# SCH_milkv-extension-board_2024-06-30.net
KiCad netlist of a schematic drawn in EasyEDA
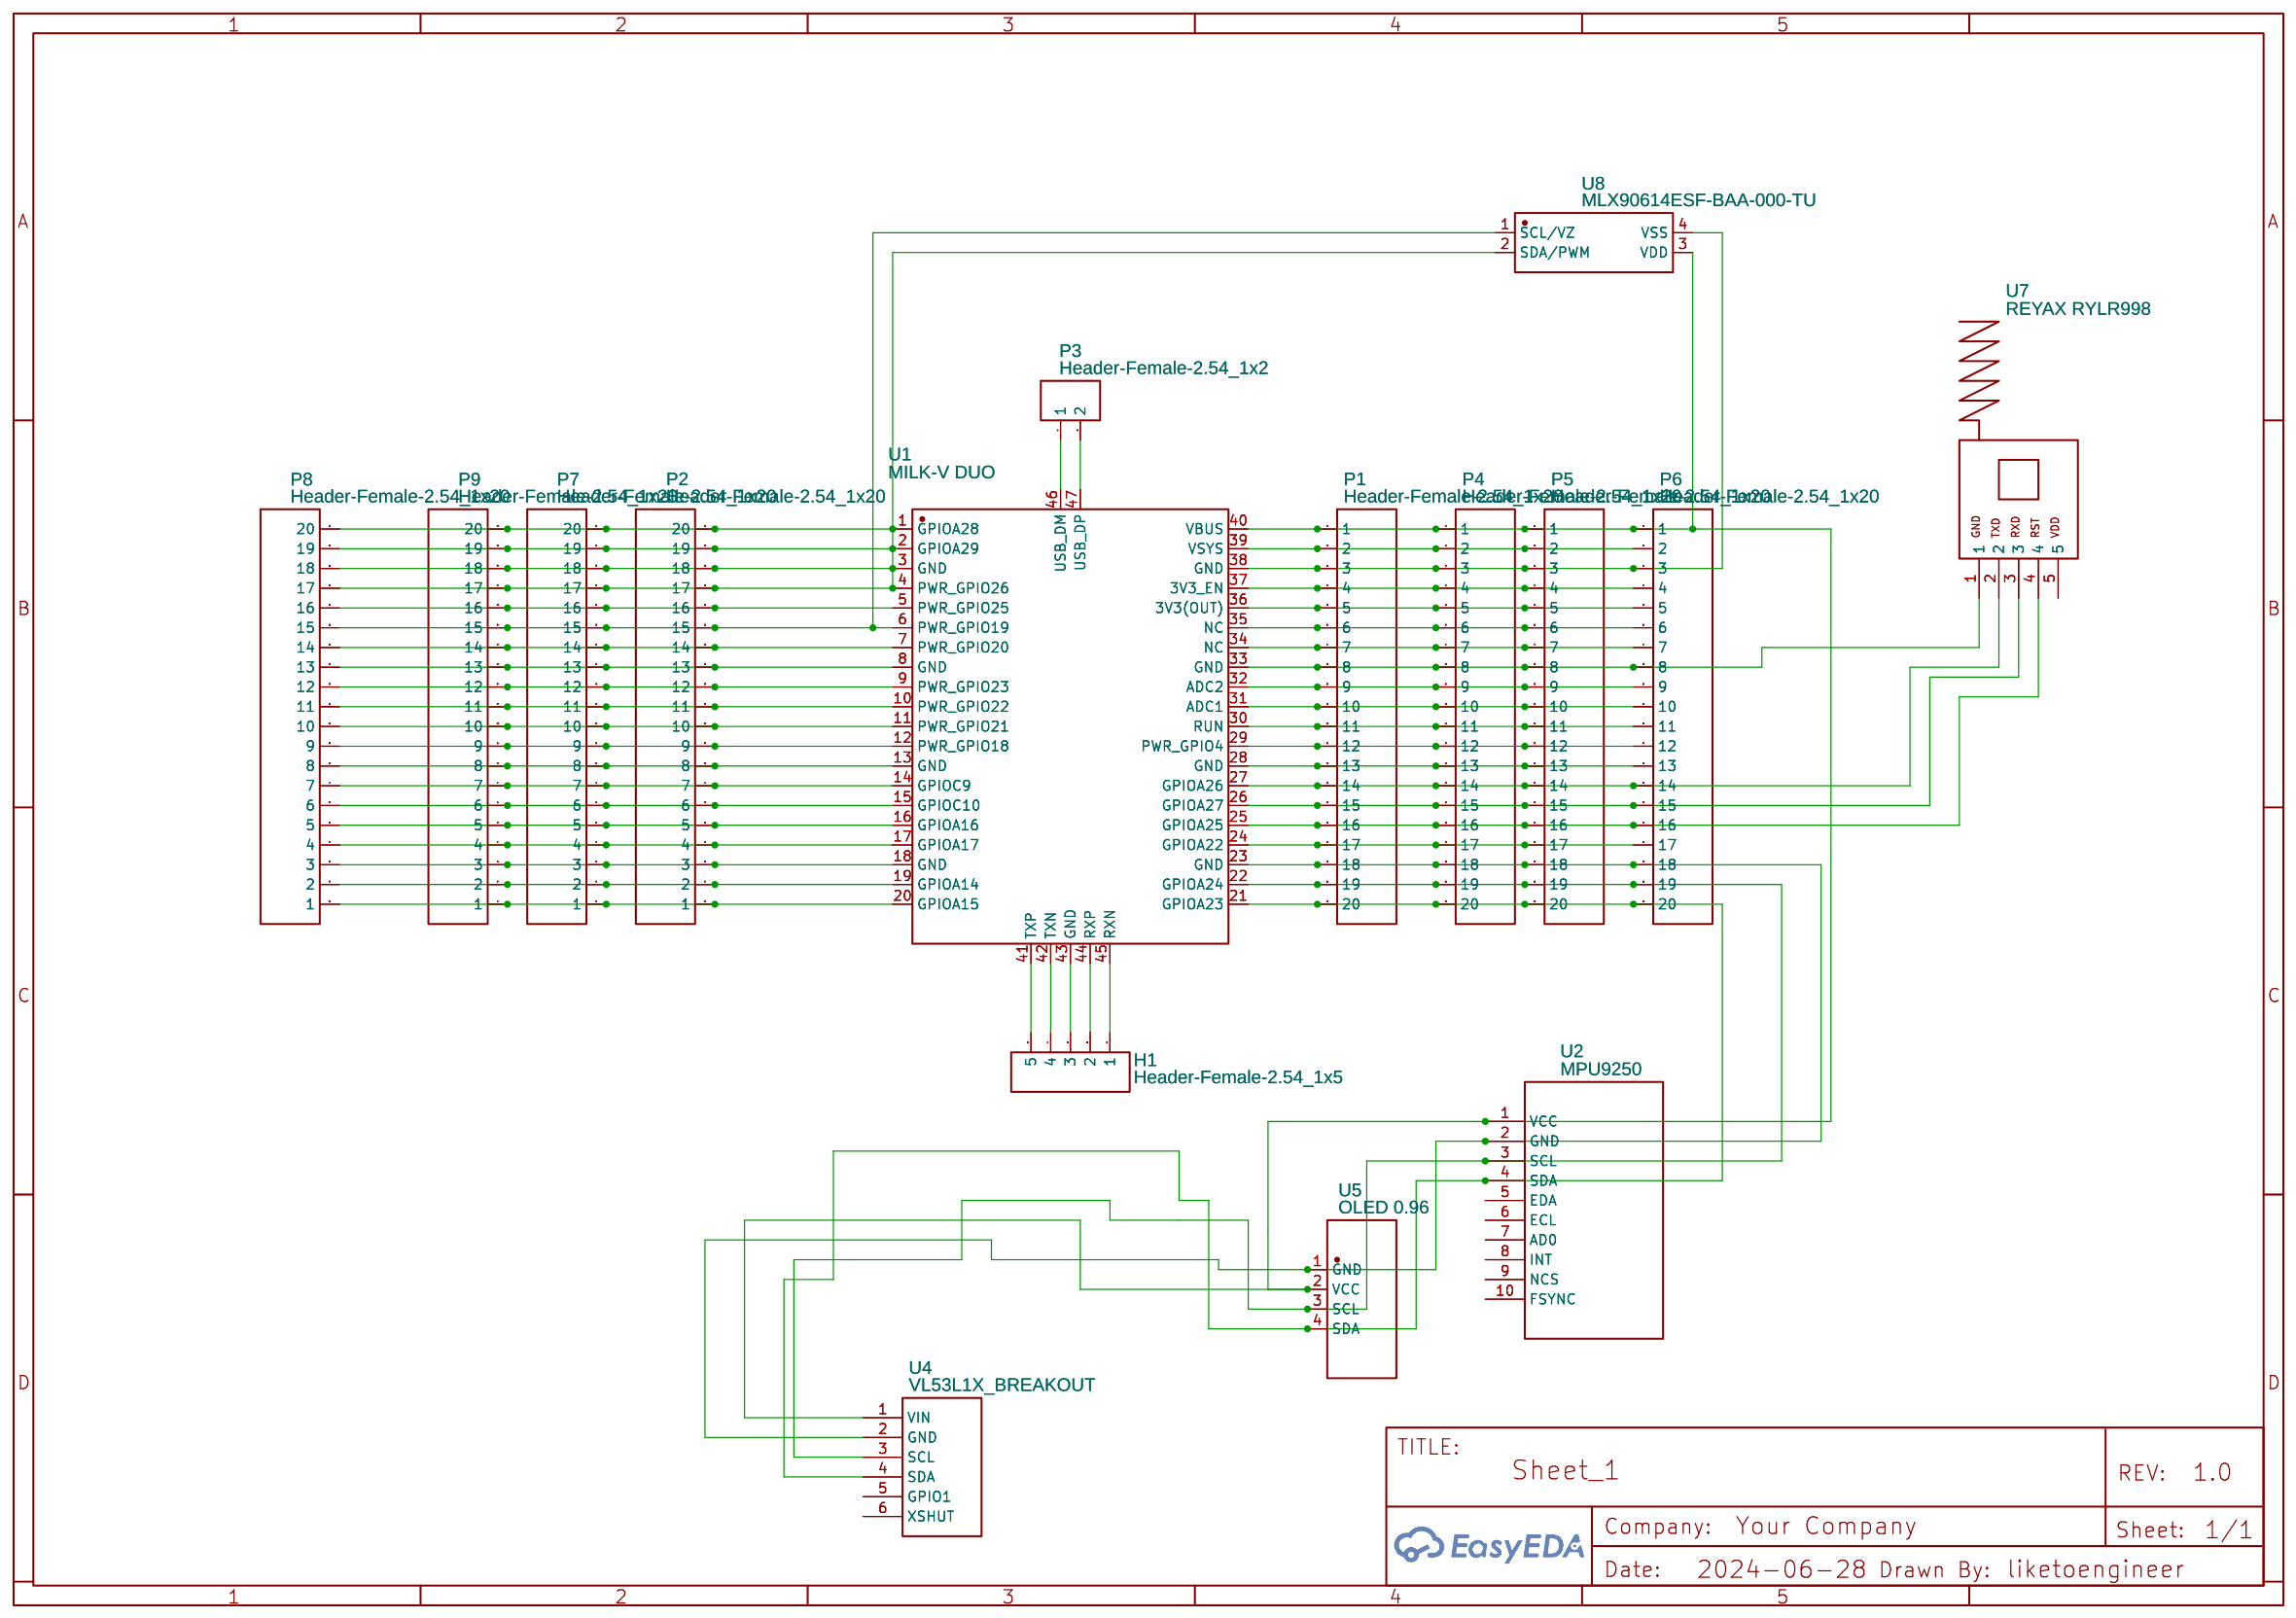
[diagram p0: schematic sheet]

(export (version "E")
  (design (tool "Eeschema 10.0.6"))
  (components
    (comp (ref "H1")
      (value "Header-Female-2.54_1x5")
      (fields (field (name "Manufacturer Part") "2.54-1*5P母") (field (name "Manufacturer") "BOOMELE(博穆精密)"))
      (libsource (lib "") (part "Header-Female-2.54_1x5"))
    )
    (comp (ref "P1")
      (value "Header-Female-2.54_1x20")
      (fields (field (name "Manufacturer Part") "2.54-1*20P母") (field (name "Manufacturer") "BOOMELE(博穆精密)"))
      (libsource (lib "") (part "Header-Female-2.54_1x20"))
    )
    (comp (ref "P2")
      (value "Header-Female-2.54_1x20")
      (fields (field (name "Manufacturer Part") "2.54-1*20P母") (field (name "Manufacturer") "BOOMELE(博穆精密)"))
      (libsource (lib "") (part "Header-Female-2.54_1x20_1"))
    )
    (comp (ref "P3")
      (value "Header-Female-2.54_1x2")
      (fields (field (name "Manufacturer Part") "2.54-1*2P母") (field (name "Manufacturer") "BOOMELE(博穆精密)"))
      (libsource (lib "") (part "Header-Female-2.54_1x2"))
    )
    (comp (ref "P4")
      (value "Header-Female-2.54_1x20")
      (fields (field (name "Manufacturer Part") "2.54-1*20P母") (field (name "Manufacturer") "BOOMELE(博穆精密)"))
      (libsource (lib "") (part "Header-Female-2.54_1x20"))
    )
    (comp (ref "P5")
      (value "Header-Female-2.54_1x20")
      (fields (field (name "Manufacturer Part") "2.54-1*20P母") (field (name "Manufacturer") "BOOMELE(博穆精密)"))
      (libsource (lib "") (part "Header-Female-2.54_1x20"))
    )
    (comp (ref "P6")
      (value "Header-Female-2.54_1x20")
      (fields (field (name "Manufacturer Part") "2.54-1*20P母") (field (name "Manufacturer") "BOOMELE(博穆精密)"))
      (libsource (lib "") (part "Header-Female-2.54_1x20"))
    )
    (comp (ref "P7")
      (value "Header-Female-2.54_1x20")
      (fields (field (name "Manufacturer Part") "2.54-1*20P母") (field (name "Manufacturer") "BOOMELE(博穆精密)"))
      (libsource (lib "") (part "Header-Female-2.54_1x20_1"))
    )
    (comp (ref "P8")
      (value "Header-Female-2.54_1x20")
      (fields (field (name "Manufacturer Part") "2.54-1*20P母") (field (name "Manufacturer") "BOOMELE(博穆精密)"))
      (libsource (lib "") (part "Header-Female-2.54_1x20_1"))
    )
    (comp (ref "P9")
      (value "Header-Female-2.54_1x20")
      (fields (field (name "Manufacturer Part") "2.54-1*20P母") (field (name "Manufacturer") "BOOMELE(博穆精密)"))
      (libsource (lib "") (part "Header-Female-2.54_1x20_1"))
    )
    (comp (ref "U1")
      (value "MILK-V DUO")
      (fields (field (name "Manufacturer Part") "Milk-V Duo"))
      (libsource (lib "") (part "MILK-V DUO"))
    )
    (comp (ref "U2") (value "MPU9250") (libsource (lib "") (part "MPU9250")))
    (comp (ref "U4")
      (value "VL53L1X_BREAKOUT")
      (fields (field (name "Manufacturer Part") "VL53L0X Time-of-Flight Distance Sensor VL53L0X"))
      (libsource (lib "") (part "VL53L1X_BREAKOUT"))
    )
    (comp (ref "U5")
      (value "OLED 0.96")
      (fields
        (field (name "Manufacturer Part") "ZJY096S0700BG01蓝色")
        (field (name "Manufacturer") "郑州中景园电子技术有限公司")
      )
      (libsource (lib "") (part "OLED 0.96"))
    )
    (comp (ref "U7")
      (value "REYAX RYLR998")
      (fields (field (name "Manufacturer Part") "RYLR998") (field (name "Manufacturer") "REYAX"))
      (libsource (lib "") (part "REYAX RYLR998"))
    )
    (comp (ref "U8")
      (value "MLX90614ESF-BAA-000-TU")
      (fields (field (name "Manufacturer") "Melexis(比利时迈来芯)"))
      (libsource (lib "") (part "MLX90614ESF-BAA-000-TU"))
    )
  )
  (nets
    (net (code "1") (name "Net-(H1-Pad3)") (class "Default")
      (node (ref "H1") (pin "3") (pinfunction "3_3") (pintype "input"))
      (node (ref "U1") (pin "43") (pinfunction "GND_43") (pintype "unspecified"))
    )
    (net (code "2") (name "Net-(P1-Pad6)") (class "Default")
      (node (ref "P1") (pin "6") (pinfunction "6_6") (pintype "input"))
      (node (ref "P4") (pin "6") (pinfunction "6_6") (pintype "input"))
      (node (ref "P5") (pin "6") (pinfunction "6_6") (pintype "input"))
      (node (ref "P6") (pin "6") (pinfunction "6_6") (pintype "input"))
      (node (ref "U1") (pin "35") (pinfunction "NC_35") (pintype "unspecified"))
    )
    (net (code "3") (name "Net-(P1-Pad7)") (class "Default")
      (node (ref "P1") (pin "7") (pinfunction "7_7") (pintype "input"))
      (node (ref "P4") (pin "7") (pinfunction "7_7") (pintype "input"))
      (node (ref "P5") (pin "7") (pinfunction "7_7") (pintype "input"))
      (node (ref "P6") (pin "7") (pinfunction "7_7") (pintype "input"))
      (node (ref "U1") (pin "34") (pinfunction "NC_34") (pintype "unspecified"))
    )
    (net (code "4") (name "Net-(P1-Pad8)") (class "Default")
      (node (ref "P1") (pin "8") (pinfunction "8_8") (pintype "input"))
      (node (ref "P4") (pin "8") (pinfunction "8_8") (pintype "input"))
      (node (ref "P5") (pin "8") (pinfunction "8_8") (pintype "input"))
      (node (ref "P6") (pin "8") (pinfunction "8_8") (pintype "input"))
      (node (ref "U1") (pin "33") (pinfunction "GND_33") (pintype "unspecified"))
      (node (ref "U7") (pin "1") (pinfunction "1_1") (pintype "unspecified"))
    )
    (net (code "5") (name "Net-(P1-Pad13)") (class "Default")
      (node (ref "P1") (pin "13") (pinfunction "13_13") (pintype "input"))
      (node (ref "P4") (pin "13") (pinfunction "13_13") (pintype "input"))
      (node (ref "P5") (pin "13") (pinfunction "13_13") (pintype "input"))
      (node (ref "P6") (pin "13") (pinfunction "13_13") (pintype "input"))
      (node (ref "U1") (pin "28") (pinfunction "GND_28") (pintype "unspecified"))
    )
    (net (code "6") (name "Net-(P2-Pad3)") (class "Default")
      (node (ref "P2") (pin "3") (pinfunction "3_3") (pintype "input"))
      (node (ref "P7") (pin "3") (pinfunction "3_3") (pintype "input"))
      (node (ref "P8") (pin "3") (pinfunction "3_3") (pintype "input"))
      (node (ref "P9") (pin "3") (pinfunction "3_3") (pintype "input"))
      (node (ref "U1") (pin "18") (pinfunction "GND_18") (pintype "unspecified"))
    )
    (net (code "7") (name "Net-(P2-Pad8)") (class "Default")
      (node (ref "P2") (pin "8") (pinfunction "8_8") (pintype "input"))
      (node (ref "P7") (pin "8") (pinfunction "8_8") (pintype "input"))
      (node (ref "P8") (pin "8") (pinfunction "8_8") (pintype "input"))
      (node (ref "P9") (pin "8") (pinfunction "8_8") (pintype "input"))
      (node (ref "U1") (pin "13") (pinfunction "GND_13") (pintype "unspecified"))
    )
    (net (code "8") (name "Net-(P2-Pad13)") (class "Default")
      (node (ref "P2") (pin "13") (pinfunction "13_13") (pintype "input"))
      (node (ref "P7") (pin "13") (pinfunction "13_13") (pintype "input"))
      (node (ref "P8") (pin "13") (pinfunction "13_13") (pintype "input"))
      (node (ref "P9") (pin "13") (pinfunction "13_13") (pintype "input"))
      (node (ref "U1") (pin "8") (pinfunction "GND_8") (pintype "unspecified"))
    )
    (net (code "9") (name "Net-(U1-3V3(OUT))") (class "Default")
      (node (ref "P1") (pin "5") (pinfunction "5_5") (pintype "input"))
      (node (ref "P4") (pin "5") (pinfunction "5_5") (pintype "input"))
      (node (ref "P5") (pin "5") (pinfunction "5_5") (pintype "input"))
      (node (ref "P6") (pin "5") (pinfunction "5_5") (pintype "input"))
      (node (ref "U1") (pin "36") (pinfunction "3V3(OUT)_36") (pintype "unspecified"))
    )
    (net (code "10") (name "Net-(U1-3V3_EN)") (class "Default")
      (node (ref "P1") (pin "4") (pinfunction "4_4") (pintype "input"))
      (node (ref "P4") (pin "4") (pinfunction "4_4") (pintype "input"))
      (node (ref "P5") (pin "4") (pinfunction "4_4") (pintype "input"))
      (node (ref "P6") (pin "4") (pinfunction "4_4") (pintype "input"))
      (node (ref "U1") (pin "37") (pinfunction "3V3_EN_37") (pintype "unspecified"))
    )
    (net (code "11") (name "Net-(U1-ADC1)") (class "Default")
      (node (ref "P1") (pin "10") (pinfunction "10_10") (pintype "input"))
      (node (ref "P4") (pin "10") (pinfunction "10_10") (pintype "input"))
      (node (ref "P5") (pin "10") (pinfunction "10_10") (pintype "input"))
      (node (ref "P6") (pin "10") (pinfunction "10_10") (pintype "input"))
      (node (ref "U1") (pin "31") (pinfunction "ADC1_31") (pintype "unspecified"))
    )
    (net (code "12") (name "Net-(U1-ADC2)") (class "Default")
      (node (ref "P1") (pin "9") (pinfunction "9_9") (pintype "input"))
      (node (ref "P4") (pin "9") (pinfunction "9_9") (pintype "input"))
      (node (ref "P5") (pin "9") (pinfunction "9_9") (pintype "input"))
      (node (ref "P6") (pin "9") (pinfunction "9_9") (pintype "input"))
      (node (ref "U1") (pin "32") (pinfunction "ADC2_32") (pintype "unspecified"))
    )
    (net (code "13") (name "Net-(U1-GPIOA14)") (class "Default")
      (node (ref "P2") (pin "2") (pinfunction "2_2") (pintype "input"))
      (node (ref "P7") (pin "2") (pinfunction "2_2") (pintype "input"))
      (node (ref "P8") (pin "2") (pinfunction "2_2") (pintype "input"))
      (node (ref "P9") (pin "2") (pinfunction "2_2") (pintype "input"))
      (node (ref "U1") (pin "19") (pinfunction "GPIOA14_19") (pintype "unspecified"))
    )
    (net (code "14") (name "Net-(U1-GPIOA15)") (class "Default")
      (node (ref "P2") (pin "1") (pinfunction "1_1") (pintype "input"))
      (node (ref "P7") (pin "1") (pinfunction "1_1") (pintype "input"))
      (node (ref "P8") (pin "1") (pinfunction "1_1") (pintype "input"))
      (node (ref "P9") (pin "1") (pinfunction "1_1") (pintype "input"))
      (node (ref "U1") (pin "20") (pinfunction "GPIOA15_20") (pintype "unspecified"))
    )
    (net (code "15") (name "Net-(U1-GPIOA16)") (class "Default")
      (node (ref "P2") (pin "5") (pinfunction "5_5") (pintype "input"))
      (node (ref "P7") (pin "5") (pinfunction "5_5") (pintype "input"))
      (node (ref "P8") (pin "5") (pinfunction "5_5") (pintype "input"))
      (node (ref "P9") (pin "5") (pinfunction "5_5") (pintype "input"))
      (node (ref "U1") (pin "16") (pinfunction "GPIOA16_16") (pintype "unspecified"))
    )
    (net (code "16") (name "Net-(U1-GPIOA17)") (class "Default")
      (node (ref "P2") (pin "4") (pinfunction "4_4") (pintype "input"))
      (node (ref "P7") (pin "4") (pinfunction "4_4") (pintype "input"))
      (node (ref "P8") (pin "4") (pinfunction "4_4") (pintype "input"))
      (node (ref "P9") (pin "4") (pinfunction "4_4") (pintype "input"))
      (node (ref "U1") (pin "17") (pinfunction "GPIOA17_17") (pintype "unspecified"))
    )
    (net (code "17") (name "Net-(U1-GPIOA22)") (class "Default")
      (node (ref "P1") (pin "17") (pinfunction "17_17") (pintype "input"))
      (node (ref "P4") (pin "17") (pinfunction "17_17") (pintype "input"))
      (node (ref "P5") (pin "17") (pinfunction "17_17") (pintype "input"))
      (node (ref "P6") (pin "17") (pinfunction "17_17") (pintype "input"))
      (node (ref "U1") (pin "24") (pinfunction "GPIOA22_24") (pintype "unspecified"))
    )
    (net (code "18") (name "Net-(U1-GPIOA23)") (class "Default")
      (node (ref "P1") (pin "20") (pinfunction "20_20") (pintype "input"))
      (node (ref "P4") (pin "20") (pinfunction "20_20") (pintype "input"))
      (node (ref "P5") (pin "20") (pinfunction "20_20") (pintype "input"))
      (node (ref "P6") (pin "20") (pinfunction "20_20") (pintype "input"))
      (node (ref "U1") (pin "21") (pinfunction "GPIOA23_21") (pintype "unspecified"))
      (node (ref "U2") (pin "4") (pinfunction "SDA_4") (pintype "unspecified"))
      (node (ref "U4") (pin "4") (pinfunction "SDA_4") (pintype "unspecified"))
      (node (ref "U5") (pin "4") (pinfunction "SDA_4") (pintype "unspecified"))
    )
    (net (code "19") (name "Net-(U1-GPIOA24)") (class "Default")
      (node (ref "P1") (pin "19") (pinfunction "19_19") (pintype "input"))
      (node (ref "P4") (pin "19") (pinfunction "19_19") (pintype "input"))
      (node (ref "P5") (pin "19") (pinfunction "19_19") (pintype "input"))
      (node (ref "P6") (pin "19") (pinfunction "19_19") (pintype "input"))
      (node (ref "U1") (pin "22") (pinfunction "GPIOA24_22") (pintype "unspecified"))
      (node (ref "U2") (pin "3") (pinfunction "SCL_3") (pintype "unspecified"))
      (node (ref "U4") (pin "3") (pinfunction "SCL_3") (pintype "unspecified"))
      (node (ref "U5") (pin "3") (pinfunction "SCL_3") (pintype "unspecified"))
    )
    (net (code "20") (name "Net-(U1-GPIOA25)") (class "Default")
      (node (ref "P1") (pin "16") (pinfunction "16_16") (pintype "input"))
      (node (ref "P4") (pin "16") (pinfunction "16_16") (pintype "input"))
      (node (ref "P5") (pin "16") (pinfunction "16_16") (pintype "input"))
      (node (ref "P6") (pin "16") (pinfunction "16_16") (pintype "input"))
      (node (ref "U1") (pin "25") (pinfunction "GPIOA25_25") (pintype "unspecified"))
      (node (ref "U7") (pin "4") (pinfunction "4_4") (pintype "unspecified"))
    )
    (net (code "21") (name "Net-(U1-GPIOA26)") (class "Default")
      (node (ref "P1") (pin "14") (pinfunction "14_14") (pintype "input"))
      (node (ref "P4") (pin "14") (pinfunction "14_14") (pintype "input"))
      (node (ref "P5") (pin "14") (pinfunction "14_14") (pintype "input"))
      (node (ref "P6") (pin "14") (pinfunction "14_14") (pintype "input"))
      (node (ref "U1") (pin "27") (pinfunction "GPIOA26_27") (pintype "unspecified"))
      (node (ref "U7") (pin "2") (pinfunction "2_2") (pintype "unspecified"))
    )
    (net (code "22") (name "Net-(U1-GPIOA27)") (class "Default")
      (node (ref "P1") (pin "15") (pinfunction "15_15") (pintype "input"))
      (node (ref "P4") (pin "15") (pinfunction "15_15") (pintype "input"))
      (node (ref "P5") (pin "15") (pinfunction "15_15") (pintype "input"))
      (node (ref "P6") (pin "15") (pinfunction "15_15") (pintype "input"))
      (node (ref "U1") (pin "26") (pinfunction "GPIOA27_26") (pintype "unspecified"))
      (node (ref "U7") (pin "3") (pinfunction "3_3") (pintype "unspecified"))
    )
    (net (code "23") (name "Net-(U1-GPIOA28)") (class "Default")
      (node (ref "P2") (pin "17") (pinfunction "17_17") (pintype "input"))
      (node (ref "P2") (pin "18") (pinfunction "18_18") (pintype "input"))
      (node (ref "P2") (pin "19") (pinfunction "19_19") (pintype "input"))
      (node (ref "P2") (pin "20") (pinfunction "20_20") (pintype "input"))
      (node (ref "P7") (pin "17") (pinfunction "17_17") (pintype "input"))
      (node (ref "P7") (pin "18") (pinfunction "18_18") (pintype "input"))
      (node (ref "P7") (pin "19") (pinfunction "19_19") (pintype "input"))
      (node (ref "P7") (pin "20") (pinfunction "20_20") (pintype "input"))
      (node (ref "P8") (pin "17") (pinfunction "17_17") (pintype "input"))
      (node (ref "P8") (pin "18") (pinfunction "18_18") (pintype "input"))
      (node (ref "P8") (pin "19") (pinfunction "19_19") (pintype "input"))
      (node (ref "P8") (pin "20") (pinfunction "20_20") (pintype "input"))
      (node (ref "P9") (pin "17") (pinfunction "17_17") (pintype "input"))
      (node (ref "P9") (pin "18") (pinfunction "18_18") (pintype "input"))
      (node (ref "P9") (pin "19") (pinfunction "19_19") (pintype "input"))
      (node (ref "P9") (pin "20") (pinfunction "20_20") (pintype "input"))
      (node (ref "U1") (pin "1") (pinfunction "GPIOA28_1") (pintype "unspecified"))
      (node (ref "U1") (pin "2") (pinfunction "GPIOA29_2") (pintype "unspecified"))
      (node (ref "U1") (pin "3") (pinfunction "GND_3") (pintype "unspecified"))
      (node (ref "U1") (pin "4") (pinfunction "PWR_GPIO26_4") (pintype "unspecified"))
      (node (ref "U8") (pin "2") (pinfunction "SDA/PWM_2") (pintype "unspecified"))
    )
    (net (code "24") (name "Net-(U1-GPIOC9)") (class "Default")
      (node (ref "P2") (pin "7") (pinfunction "7_7") (pintype "input"))
      (node (ref "P7") (pin "7") (pinfunction "7_7") (pintype "input"))
      (node (ref "P8") (pin "7") (pinfunction "7_7") (pintype "input"))
      (node (ref "P9") (pin "7") (pinfunction "7_7") (pintype "input"))
      (node (ref "U1") (pin "14") (pinfunction "GPIOC9_14") (pintype "unspecified"))
    )
    (net (code "25") (name "Net-(U1-GPIOC10)") (class "Default")
      (node (ref "P2") (pin "6") (pinfunction "6_6") (pintype "input"))
      (node (ref "P7") (pin "6") (pinfunction "6_6") (pintype "input"))
      (node (ref "P8") (pin "6") (pinfunction "6_6") (pintype "input"))
      (node (ref "P9") (pin "6") (pinfunction "6_6") (pintype "input"))
      (node (ref "U1") (pin "15") (pinfunction "GPIOC10_15") (pintype "unspecified"))
    )
    (net (code "26") (name "Net-(U1-PWR_GPIO4)") (class "Default")
      (node (ref "P1") (pin "12") (pinfunction "12_12") (pintype "input"))
      (node (ref "P4") (pin "12") (pinfunction "12_12") (pintype "input"))
      (node (ref "P5") (pin "12") (pinfunction "12_12") (pintype "input"))
      (node (ref "P6") (pin "12") (pinfunction "12_12") (pintype "input"))
      (node (ref "U1") (pin "29") (pinfunction "PWR_GPIO4_29") (pintype "unspecified"))
    )
    (net (code "27") (name "Net-(U1-PWR_GPIO18)") (class "Default")
      (node (ref "P2") (pin "9") (pinfunction "9_9") (pintype "input"))
      (node (ref "P7") (pin "9") (pinfunction "9_9") (pintype "input"))
      (node (ref "P8") (pin "9") (pinfunction "9_9") (pintype "input"))
      (node (ref "P9") (pin "9") (pinfunction "9_9") (pintype "input"))
      (node (ref "U1") (pin "12") (pinfunction "PWR_GPIO18_12") (pintype "unspecified"))
    )
    (net (code "28") (name "Net-(U1-PWR_GPIO19)") (class "Default")
      (node (ref "P2") (pin "15") (pinfunction "15_15") (pintype "input"))
      (node (ref "P7") (pin "15") (pinfunction "15_15") (pintype "input"))
      (node (ref "P8") (pin "15") (pinfunction "15_15") (pintype "input"))
      (node (ref "P9") (pin "15") (pinfunction "15_15") (pintype "input"))
      (node (ref "U1") (pin "6") (pinfunction "PWR_GPIO19_6") (pintype "unspecified"))
      (node (ref "U8") (pin "1") (pinfunction "SCL/VZ_1") (pintype "unspecified"))
    )
    (net (code "29") (name "Net-(U1-PWR_GPIO20)") (class "Default")
      (node (ref "P2") (pin "14") (pinfunction "14_14") (pintype "input"))
      (node (ref "P7") (pin "14") (pinfunction "14_14") (pintype "input"))
      (node (ref "P8") (pin "14") (pinfunction "14_14") (pintype "input"))
      (node (ref "P9") (pin "14") (pinfunction "14_14") (pintype "input"))
      (node (ref "U1") (pin "7") (pinfunction "PWR_GPIO20_7") (pintype "unspecified"))
    )
    (net (code "30") (name "Net-(U1-PWR_GPIO21)") (class "Default")
      (node (ref "P2") (pin "10") (pinfunction "10_10") (pintype "input"))
      (node (ref "P7") (pin "10") (pinfunction "10_10") (pintype "input"))
      (node (ref "P8") (pin "10") (pinfunction "10_10") (pintype "input"))
      (node (ref "P9") (pin "10") (pinfunction "10_10") (pintype "input"))
      (node (ref "U1") (pin "11") (pinfunction "PWR_GPIO21_11") (pintype "unspecified"))
    )
    (net (code "31") (name "Net-(U1-PWR_GPIO22)") (class "Default")
      (node (ref "P2") (pin "11") (pinfunction "11_11") (pintype "input"))
      (node (ref "P7") (pin "11") (pinfunction "11_11") (pintype "input"))
      (node (ref "P8") (pin "11") (pinfunction "11_11") (pintype "input"))
      (node (ref "P9") (pin "11") (pinfunction "11_11") (pintype "input"))
      (node (ref "U1") (pin "10") (pinfunction "PWR_GPIO22_10") (pintype "unspecified"))
    )
    (net (code "32") (name "Net-(U1-PWR_GPIO23)") (class "Default")
      (node (ref "P2") (pin "12") (pinfunction "12_12") (pintype "input"))
      (node (ref "P7") (pin "12") (pinfunction "12_12") (pintype "input"))
      (node (ref "P8") (pin "12") (pinfunction "12_12") (pintype "input"))
      (node (ref "P9") (pin "12") (pinfunction "12_12") (pintype "input"))
      (node (ref "U1") (pin "9") (pinfunction "PWR_GPIO23_9") (pintype "unspecified"))
    )
    (net (code "33") (name "Net-(U1-PWR_GPIO25)") (class "Default")
      (node (ref "P2") (pin "16") (pinfunction "16_16") (pintype "input"))
      (node (ref "P7") (pin "16") (pinfunction "16_16") (pintype "input"))
      (node (ref "P8") (pin "16") (pinfunction "16_16") (pintype "input"))
      (node (ref "P9") (pin "16") (pinfunction "16_16") (pintype "input"))
      (node (ref "U1") (pin "5") (pinfunction "PWR_GPIO25_5") (pintype "unspecified"))
    )
    (net (code "34") (name "Net-(U1-RUN)") (class "Default")
      (node (ref "P1") (pin "11") (pinfunction "11_11") (pintype "input"))
      (node (ref "P4") (pin "11") (pinfunction "11_11") (pintype "input"))
      (node (ref "P5") (pin "11") (pinfunction "11_11") (pintype "input"))
      (node (ref "P6") (pin "11") (pinfunction "11_11") (pintype "input"))
      (node (ref "U1") (pin "30") (pinfunction "RUN_30") (pintype "unspecified"))
    )
    (net (code "35") (name "Net-(U1-RXN)") (class "Default")
      (node (ref "H1") (pin "1") (pinfunction "1_1") (pintype "input"))
      (node (ref "U1") (pin "45") (pinfunction "RXN_45") (pintype "unspecified"))
    )
    (net (code "36") (name "Net-(U1-RXP)") (class "Default")
      (node (ref "H1") (pin "2") (pinfunction "2_2") (pintype "input"))
      (node (ref "U1") (pin "44") (pinfunction "RXP_44") (pintype "unspecified"))
    )
    (net (code "37") (name "Net-(U1-TXN)") (class "Default")
      (node (ref "H1") (pin "4") (pinfunction "4_4") (pintype "input"))
      (node (ref "U1") (pin "42") (pinfunction "TXN_42") (pintype "unspecified"))
    )
    (net (code "38") (name "Net-(U1-TXP)") (class "Default")
      (node (ref "H1") (pin "5") (pinfunction "5_5") (pintype "input"))
      (node (ref "U1") (pin "41") (pinfunction "TXP_41") (pintype "unspecified"))
    )
    (net (code "39") (name "Net-(U1-USB_DM)") (class "Default")
      (node (ref "P3") (pin "1") (pinfunction "1_1") (pintype "input"))
      (node (ref "U1") (pin "46") (pinfunction "USB_DM_46") (pintype "unspecified"))
    )
    (net (code "40") (name "Net-(U1-USB_DP)") (class "Default")
      (node (ref "P3") (pin "2") (pinfunction "2_2") (pintype "input"))
      (node (ref "U1") (pin "47") (pinfunction "USB_DP_47") (pintype "unspecified"))
    )
    (net (code "41") (name "Net-(U1-VBUS)") (class "Default")
      (node (ref "P1") (pin "1") (pinfunction "1_1") (pintype "input"))
      (node (ref "P4") (pin "1") (pinfunction "1_1") (pintype "input"))
      (node (ref "P5") (pin "1") (pinfunction "1_1") (pintype "input"))
      (node (ref "P6") (pin "1") (pinfunction "1_1") (pintype "input"))
      (node (ref "U1") (pin "40") (pinfunction "VBUS_40") (pintype "unspecified"))
      (node (ref "U2") (pin "1") (pinfunction "VCC_1") (pintype "unspecified"))
      (node (ref "U4") (pin "1") (pinfunction "VIN_1") (pintype "unspecified"))
      (node (ref "U5") (pin "2") (pinfunction "VCC_2") (pintype "unspecified"))
      (node (ref "U8") (pin "3") (pinfunction "VDD_3") (pintype "unspecified"))
    )
    (net (code "42") (name "Net-(U1-VSYS)") (class "Default")
      (node (ref "P1") (pin "2") (pinfunction "2_2") (pintype "input"))
      (node (ref "P4") (pin "2") (pinfunction "2_2") (pintype "input"))
      (node (ref "P5") (pin "2") (pinfunction "2_2") (pintype "input"))
      (node (ref "P6") (pin "2") (pinfunction "2_2") (pintype "input"))
      (node (ref "U1") (pin "39") (pinfunction "VSYS_39") (pintype "unspecified"))
    )
    (net (code "43") (name "Net-(U2-GND)") (class "Default")
      (node (ref "P1") (pin "18") (pinfunction "18_18") (pintype "input"))
      (node (ref "P4") (pin "18") (pinfunction "18_18") (pintype "input"))
      (node (ref "P5") (pin "18") (pinfunction "18_18") (pintype "input"))
      (node (ref "P6") (pin "18") (pinfunction "18_18") (pintype "input"))
      (node (ref "U1") (pin "23") (pinfunction "GND_23") (pintype "unspecified"))
      (node (ref "U2") (pin "2") (pinfunction "GND_2") (pintype "unspecified"))
      (node (ref "U4") (pin "2") (pinfunction "GND_2") (pintype "unspecified"))
      (node (ref "U5") (pin "1") (pinfunction "GND_1") (pintype "unspecified"))
    )
    (net (code "44") (name "Net-(U8-VSS)") (class "Default")
      (node (ref "P1") (pin "3") (pinfunction "3_3") (pintype "input"))
      (node (ref "P4") (pin "3") (pinfunction "3_3") (pintype "input"))
      (node (ref "P5") (pin "3") (pinfunction "3_3") (pintype "input"))
      (node (ref "P6") (pin "3") (pinfunction "3_3") (pintype "input"))
      (node (ref "U1") (pin "38") (pinfunction "GND_38") (pintype "unspecified"))
      (node (ref "U8") (pin "4") (pinfunction "VSS_4") (pintype "unspecified"))
    )
    (net (code "45") (name "unconnected-(U2-AD0-Pad7)") (class "Default")
      (node (ref "U2") (pin "7") (pinfunction "AD0_7") (pintype "unspecified"))
    )
    (net (code "46") (name "unconnected-(U2-ECL-Pad6)") (class "Default")
      (node (ref "U2") (pin "6") (pinfunction "ECL_6") (pintype "unspecified"))
    )
    (net (code "47") (name "unconnected-(U2-EDA-Pad5)") (class "Default")
      (node (ref "U2") (pin "5") (pinfunction "EDA_5") (pintype "unspecified"))
    )
    (net (code "48") (name "unconnected-(U2-FSYNC-Pad10)") (class "Default")
      (node (ref "U2") (pin "10") (pinfunction "FSYNC_10") (pintype "unspecified"))
    )
    (net (code "49") (name "unconnected-(U2-INT-Pad8)") (class "Default")
      (node (ref "U2") (pin "8") (pinfunction "INT_8") (pintype "unspecified"))
    )
    (net (code "50") (name "unconnected-(U2-NCS-Pad9)") (class "Default")
      (node (ref "U2") (pin "9") (pinfunction "NCS_9") (pintype "unspecified"))
    )
    (net (code "51") (name "unconnected-(U4-GPIO1-Pad5)") (class "Default")
      (node (ref "U4") (pin "5") (pinfunction "GPIO1_5") (pintype "unspecified"))
    )
    (net (code "52") (name "unconnected-(U4-XSHUT-Pad6)") (class "Default")
      (node (ref "U4") (pin "6") (pinfunction "XSHUT_6") (pintype "unspecified"))
    )
    (net (code "53") (name "unconnected-(U7-Pad5)") (class "Default")
      (node (ref "U7") (pin "5") (pinfunction "5_5") (pintype "unspecified"))
    )
  )
)
